# SHEET1.net
KiCad netlist of a schematic drawn in Altium Designer
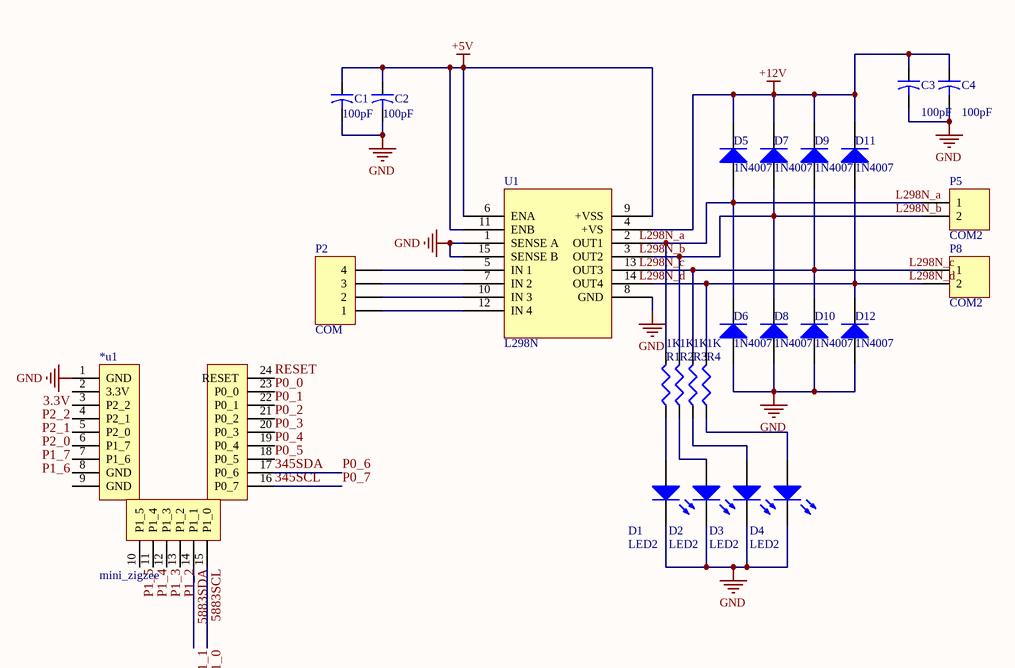
[diagram p0: SHEET1.SCHDOC]

(export (version "E")
  (design (tool "Eeschema 10.0.6"))
  (components
    (comp (ref "*u1")
      (value "mini_zigzee")
      (footprint "mini_zigbee")
      (libsource (lib "*") (part "mini_zigzee"))
    )
    (comp (ref "C1")
      (value "100pF")
      (footprint "CAPR5-4X5")
      (description "Capacitor")
      (fields (field (name "PUBLISHER") "Altium Limited"))
      (libsource (lib "Miscellaneous Devices") (part "Cap2"))
    )
    (comp (ref "C2")
      (value "100pF")
      (footprint "CAPR5-4X5")
      (description "Capacitor")
      (fields (field (name "PUBLISHER") "Altium Limited"))
      (libsource (lib "Miscellaneous Devices") (part "Cap2"))
    )
    (comp (ref "C3")
      (value "100pF")
      (footprint "CAPR5-4X5")
      (description "Capacitor")
      (fields (field (name "PUBLISHER") "Altium Limited"))
      (libsource (lib "Miscellaneous Devices") (part "Cap2"))
    )
    (comp (ref "C4")
      (value "100pF")
      (footprint "CAPR5-4X5")
      (description "Capacitor")
      (fields (field (name "PUBLISHER") "Altium Limited"))
      (libsource (lib "Miscellaneous Devices") (part "Cap2"))
    )
    (comp (ref "D1")
      (value "LED2")
      (footprint "3.2X1.6X1.1")
      (description "Typical RED, GREEN, YELLOW, AMBER GaAs LED")
      (fields (field (name "PUBLISHER") "Altium Limited"))
      (libsource (lib "Miscellaneous Devices") (part "LED2"))
    )
    (comp (ref "D2")
      (value "LED2")
      (footprint "3.2X1.6X1.1")
      (description "Typical RED, GREEN, YELLOW, AMBER GaAs LED")
      (fields (field (name "PUBLISHER") "Altium Limited"))
      (libsource (lib "Miscellaneous Devices") (part "LED2"))
    )
    (comp (ref "D3")
      (value "LED2")
      (footprint "3.2X1.6X1.1")
      (description "Typical RED, GREEN, YELLOW, AMBER GaAs LED")
      (fields (field (name "PUBLISHER") "Altium Limited"))
      (libsource (lib "Miscellaneous Devices") (part "LED2"))
    )
    (comp (ref "D4")
      (value "LED2")
      (footprint "3.2X1.6X1.1")
      (description "Typical RED, GREEN, YELLOW, AMBER GaAs LED")
      (fields (field (name "PUBLISHER") "Altium Limited"))
      (libsource (lib "Miscellaneous Devices") (part "LED2"))
    )
    (comp (ref "D5")
      (value "1N4007")
      (footprint "DO-41")
      (description "1 Amp General Purpose Rectifier")
      (fields (field (name "PUBLISHER") "Altium Limited"))
      (libsource (lib "Miscellaneous Devices") (part "Diode 1N4007"))
    )
    (comp (ref "D6")
      (value "1N4007")
      (footprint "DO-41")
      (description "1 Amp General Purpose Rectifier")
      (fields (field (name "PUBLISHER") "Altium Limited"))
      (libsource (lib "Miscellaneous Devices") (part "Diode 1N4007"))
    )
    (comp (ref "D7")
      (value "1N4007")
      (footprint "DO-41")
      (description "1 Amp General Purpose Rectifier")
      (fields (field (name "PUBLISHER") "Altium Limited"))
      (libsource (lib "Miscellaneous Devices") (part "Diode 1N4007"))
    )
    (comp (ref "D8")
      (value "1N4007")
      (footprint "DO-41")
      (description "1 Amp General Purpose Rectifier")
      (fields (field (name "PUBLISHER") "Altium Limited"))
      (libsource (lib "Miscellaneous Devices") (part "Diode 1N4007"))
    )
    (comp (ref "D9")
      (value "1N4007")
      (footprint "DO-41")
      (description "1 Amp General Purpose Rectifier")
      (fields (field (name "PUBLISHER") "Altium Limited"))
      (libsource (lib "Miscellaneous Devices") (part "Diode 1N4007"))
    )
    (comp (ref "D10")
      (value "1N4007")
      (footprint "DO-41")
      (description "1 Amp General Purpose Rectifier")
      (fields (field (name "PUBLISHER") "Altium Limited"))
      (libsource (lib "Miscellaneous Devices") (part "Diode 1N4007"))
    )
    (comp (ref "D11")
      (value "1N4007")
      (footprint "DO-41")
      (description "1 Amp General Purpose Rectifier")
      (fields (field (name "PUBLISHER") "Altium Limited"))
      (libsource (lib "Miscellaneous Devices") (part "Diode 1N4007"))
    )
    (comp (ref "D12")
      (value "1N4007")
      (footprint "DO-41")
      (description "1 Amp General Purpose Rectifier")
      (fields (field (name "PUBLISHER") "Altium Limited"))
      (libsource (lib "Miscellaneous Devices") (part "Diode 1N4007"))
    )
    (comp (ref "P2")
      (value "COM")
      (footprint "HDR1X4")
      (description "Header, 4-Pin")
      (fields (field (name "PUBLISHER") "Altium Limited"))
      (libsource (lib "Miscellaneous Connectors") (part "Header 4"))
    )
    (comp (ref "P5")
      (value "COM2")
      (footprint "DP3")
      (description "Header, 2-Pin")
      (fields (field (name "PUBLISHER") "Altium Limited"))
      (libsource (lib "Miscellaneous Connectors") (part "Header 2"))
    )
    (comp (ref "P8")
      (value "COM2")
      (footprint "DP3")
      (description "Header, 2-Pin")
      (fields (field (name "PUBLISHER") "Altium Limited"))
      (libsource (lib "Miscellaneous Connectors") (part "Header 2"))
    )
    (comp (ref "R1")
      (value "1K")
      (footprint "J1-0603")
      (description "Resistor")
      (fields (field (name "Comment") "Res3") (field (name "PUBLISHER") "Altium Limited"))
      (libsource (lib "Miscellaneous Devices") (part "Res3"))
    )
    (comp (ref "R2")
      (value "1K")
      (footprint "J1-0603")
      (description "Resistor")
      (fields (field (name "Comment") "Res3") (field (name "PUBLISHER") "Altium Limited"))
      (libsource (lib "Miscellaneous Devices") (part "Res3"))
    )
    (comp (ref "R3")
      (value "1K")
      (footprint "J1-0603")
      (description "Resistor")
      (fields (field (name "Comment") "Res3") (field (name "PUBLISHER") "Altium Limited"))
      (libsource (lib "Miscellaneous Devices") (part "Res3"))
    )
    (comp (ref "R4")
      (value "1K")
      (footprint "J1-0603")
      (description "Resistor")
      (fields (field (name "Comment") "Res3") (field (name "PUBLISHER") "Altium Limited"))
      (libsource (lib "Miscellaneous Devices") (part "Res3"))
    )
    (comp (ref "U1") (value "L298N") (footprint "L298N - duplicate") (libsource (lib "KU1") (part "L298N")))
  )
  (nets
    (net (code "1") (name "+5V") (class "Default")
      (node (ref "C1") (pin "1") (pinfunction "1_1") (pintype "passive"))
      (node (ref "C2") (pin "1") (pinfunction "1_1") (pintype "passive"))
      (node (ref "U1") (pin "11") (pinfunction "ENB_11") (pintype "passive"))
      (node (ref "U1") (pin "6") (pinfunction "ENA_6") (pintype "passive"))
      (node (ref "U1") (pin "9") (pinfunction "+VSS_9") (pintype "passive"))
    )
    (net (code "2") (name "+12V") (class "Default")
      (node (ref "C3") (pin "1") (pinfunction "1_1") (pintype "passive"))
      (node (ref "C4") (pin "1") (pinfunction "1_1") (pintype "passive"))
      (node (ref "D11") (pin "2") (pinfunction "K_2") (pintype "passive"))
      (node (ref "D5") (pin "2") (pinfunction "K_2") (pintype "passive"))
      (node (ref "D7") (pin "2") (pinfunction "K_2") (pintype "passive"))
      (node (ref "D9") (pin "2") (pinfunction "K_2") (pintype "passive"))
      (node (ref "U1") (pin "4") (pinfunction "+VS_4") (pintype "passive"))
    )
    (net (code "3") (name "/3.3V") (class "Default")
      (node (ref "*u1") (pin "2") (pinfunction "3.3V_2") (pintype "passive"))
    )
    (net (code "4") (name "/345SCL") (class "Default")
      (node (ref "*u1") (pin "16") (pinfunction "P0_7_16") (pintype "passive"))
    )
    (net (code "5") (name "/345SDA") (class "Default")
      (node (ref "*u1") (pin "17") (pinfunction "P0_6_17") (pintype "passive"))
    )
    (net (code "6") (name "/5883SCL") (class "Default")
      (node (ref "*u1") (pin "15") (pinfunction "P1_0_15") (pintype "passive"))
    )
    (net (code "7") (name "/5883SDA") (class "Default")
      (node (ref "*u1") (pin "14") (pinfunction "P1_1_14") (pintype "passive"))
    )
    (net (code "8") (name "/L298N_a") (class "Default")
      (node (ref "D5") (pin "1") (pinfunction "A_1") (pintype "passive"))
      (node (ref "D6") (pin "2") (pinfunction "K_2") (pintype "passive"))
      (node (ref "P5") (pin "1") (pinfunction "1_1") (pintype "passive"))
      (node (ref "R1") (pin "2") (pinfunction "2_2") (pintype "passive"))
      (node (ref "U1") (pin "2") (pinfunction "OUT1_2") (pintype "passive"))
    )
    (net (code "9") (name "/L298N_b") (class "Default")
      (node (ref "D7") (pin "1") (pinfunction "A_1") (pintype "passive"))
      (node (ref "D8") (pin "2") (pinfunction "K_2") (pintype "passive"))
      (node (ref "P5") (pin "2") (pinfunction "2_2") (pintype "passive"))
      (node (ref "R2") (pin "2") (pinfunction "2_2") (pintype "passive"))
      (node (ref "U1") (pin "3") (pinfunction "OUT2_3") (pintype "passive"))
    )
    (net (code "10") (name "/L298N_c") (class "Default")
      (node (ref "D10") (pin "2") (pinfunction "K_2") (pintype "passive"))
      (node (ref "D9") (pin "1") (pinfunction "A_1") (pintype "passive"))
      (node (ref "P8") (pin "1") (pinfunction "1_1") (pintype "passive"))
      (node (ref "R3") (pin "2") (pinfunction "2_2") (pintype "passive"))
      (node (ref "U1") (pin "13") (pinfunction "OUT3_13") (pintype "passive"))
    )
    (net (code "11") (name "/L298N_d") (class "Default")
      (node (ref "D11") (pin "1") (pinfunction "A_1") (pintype "passive"))
      (node (ref "D12") (pin "2") (pinfunction "K_2") (pintype "passive"))
      (node (ref "P8") (pin "2") (pinfunction "2_2") (pintype "passive"))
      (node (ref "R4") (pin "2") (pinfunction "2_2") (pintype "passive"))
      (node (ref "U1") (pin "14") (pinfunction "OUT4_14") (pintype "passive"))
    )
    (net (code "12") (name "/P0_0") (class "Default")
      (node (ref "*u1") (pin "23") (pinfunction "P0_0_23") (pintype "passive"))
    )
    (net (code "13") (name "/P0_1") (class "Default")
      (node (ref "*u1") (pin "22") (pinfunction "P0_1_22") (pintype "passive"))
    )
    (net (code "14") (name "/P0_2") (class "Default")
      (node (ref "*u1") (pin "21") (pinfunction "P0_2_21") (pintype "passive"))
    )
    (net (code "15") (name "/P0_3") (class "Default")
      (node (ref "*u1") (pin "20") (pinfunction "P0_3_20") (pintype "passive"))
    )
    (net (code "16") (name "/P0_4") (class "Default")
      (node (ref "*u1") (pin "19") (pinfunction "P0_4_19") (pintype "passive"))
    )
    (net (code "17") (name "/P0_5") (class "Default")
      (node (ref "*u1") (pin "18") (pinfunction "P0_5_18") (pintype "passive"))
    )
    (net (code "18") (name "/P1_2") (class "Default")
      (node (ref "*u1") (pin "13") (pinfunction "P1_2_13") (pintype "passive"))
    )
    (net (code "19") (name "/P1_3") (class "Default")
      (node (ref "*u1") (pin "12") (pinfunction "P1_3_12") (pintype "passive"))
    )
    (net (code "20") (name "/P1_4") (class "Default")
      (node (ref "*u1") (pin "11") (pinfunction "P1_4_11") (pintype "passive"))
    )
    (net (code "21") (name "/P1_5") (class "Default")
      (node (ref "*u1") (pin "10") (pinfunction "P1_5_10") (pintype "passive"))
    )
    (net (code "22") (name "/P1_6") (class "Default")
      (node (ref "*u1") (pin "7") (pinfunction "P1_6_7") (pintype "passive"))
    )
    (net (code "23") (name "/P1_7") (class "Default")
      (node (ref "*u1") (pin "6") (pinfunction "P1_7_6") (pintype "passive"))
    )
    (net (code "24") (name "/P2_0") (class "Default")
      (node (ref "*u1") (pin "5") (pinfunction "P2_0_5") (pintype "passive"))
    )
    (net (code "25") (name "/P2_1") (class "Default")
      (node (ref "*u1") (pin "4") (pinfunction "P2_1_4") (pintype "passive"))
    )
    (net (code "26") (name "/P2_2") (class "Default")
      (node (ref "*u1") (pin "3") (pinfunction "P2_2_3") (pintype "passive"))
    )
    (net (code "27") (name "/RESET") (class "Default")
      (node (ref "*u1") (pin "24") (pinfunction "RESET_24") (pintype "passive"))
    )
    (net (code "28") (name "GND") (class "Default")
      (node (ref "*u1") (pin "1") (pinfunction "GND_1") (pintype "passive"))
      (node (ref "C1") (pin "2") (pinfunction "2_2") (pintype "passive"))
      (node (ref "C2") (pin "2") (pinfunction "2_2") (pintype "passive"))
      (node (ref "C3") (pin "2") (pinfunction "2_2") (pintype "passive"))
      (node (ref "C4") (pin "2") (pinfunction "2_2") (pintype "passive"))
      (node (ref "D1") (pin "2") (pinfunction "K_2") (pintype "passive"))
      (node (ref "D10") (pin "1") (pinfunction "A_1") (pintype "passive"))
      (node (ref "D12") (pin "1") (pinfunction "A_1") (pintype "passive"))
      (node (ref "D2") (pin "2") (pinfunction "K_2") (pintype "passive"))
      (node (ref "D3") (pin "2") (pinfunction "K_2") (pintype "passive"))
      (node (ref "D4") (pin "2") (pinfunction "K_2") (pintype "passive"))
      (node (ref "D6") (pin "1") (pinfunction "A_1") (pintype "passive"))
      (node (ref "D8") (pin "1") (pinfunction "A_1") (pintype "passive"))
      (node (ref "U1") (pin "1") (pinfunction "SENSE_A_1") (pintype "passive"))
      (node (ref "U1") (pin "15") (pinfunction "SENSE_B_15") (pintype "passive"))
      (node (ref "U1") (pin "8") (pinfunction "GND_8") (pintype "passive"))
    )
    (net (code "29") (name "Net-(D1-A)") (class "Default")
      (node (ref "D1") (pin "1") (pinfunction "A_1") (pintype "passive"))
      (node (ref "R1") (pin "1") (pinfunction "1_1") (pintype "passive"))
    )
    (net (code "30") (name "Net-(D2-A)") (class "Default")
      (node (ref "D2") (pin "1") (pinfunction "A_1") (pintype "passive"))
      (node (ref "R2") (pin "1") (pinfunction "1_1") (pintype "passive"))
    )
    (net (code "31") (name "Net-(D3-A)") (class "Default")
      (node (ref "D3") (pin "1") (pinfunction "A_1") (pintype "passive"))
      (node (ref "R3") (pin "1") (pinfunction "1_1") (pintype "passive"))
    )
    (net (code "32") (name "Net-(D4-A)") (class "Default")
      (node (ref "D4") (pin "1") (pinfunction "A_1") (pintype "passive"))
      (node (ref "R4") (pin "1") (pinfunction "1_1") (pintype "passive"))
    )
    (net (code "33") (name "Net-(U1-IN_1)") (class "Default")
      (node (ref "P2") (pin "4") (pinfunction "4_4") (pintype "passive"))
      (node (ref "U1") (pin "5") (pinfunction "IN_1_5") (pintype "passive"))
    )
    (net (code "34") (name "Net-(U1-IN_2)") (class "Default")
      (node (ref "P2") (pin "3") (pinfunction "3_3") (pintype "passive"))
      (node (ref "U1") (pin "7") (pinfunction "IN_2_7") (pintype "passive"))
    )
    (net (code "35") (name "Net-(U1-IN_3)") (class "Default")
      (node (ref "P2") (pin "2") (pinfunction "2_2") (pintype "passive"))
      (node (ref "U1") (pin "10") (pinfunction "IN_3_10") (pintype "passive"))
    )
    (net (code "36") (name "Net-(U1-IN_4)") (class "Default")
      (node (ref "P2") (pin "1") (pinfunction "1_1") (pintype "passive"))
      (node (ref "U1") (pin "12") (pinfunction "IN_4_12") (pintype "passive"))
    )
    (net (code "37") (name "unconnected-(*u1-GND-Pad8)") (class "Default")
      (node (ref "*u1") (pin "8") (pinfunction "GND_8") (pintype "passive"))
    )
    (net (code "38") (name "unconnected-(*u1-GND-Pad9)") (class "Default")
      (node (ref "*u1") (pin "9") (pinfunction "GND_9") (pintype "passive"))
    )
  )
)
